# MegaAMP_Mk1.net
KiCad netlist of a schematic drawn in EAGLE
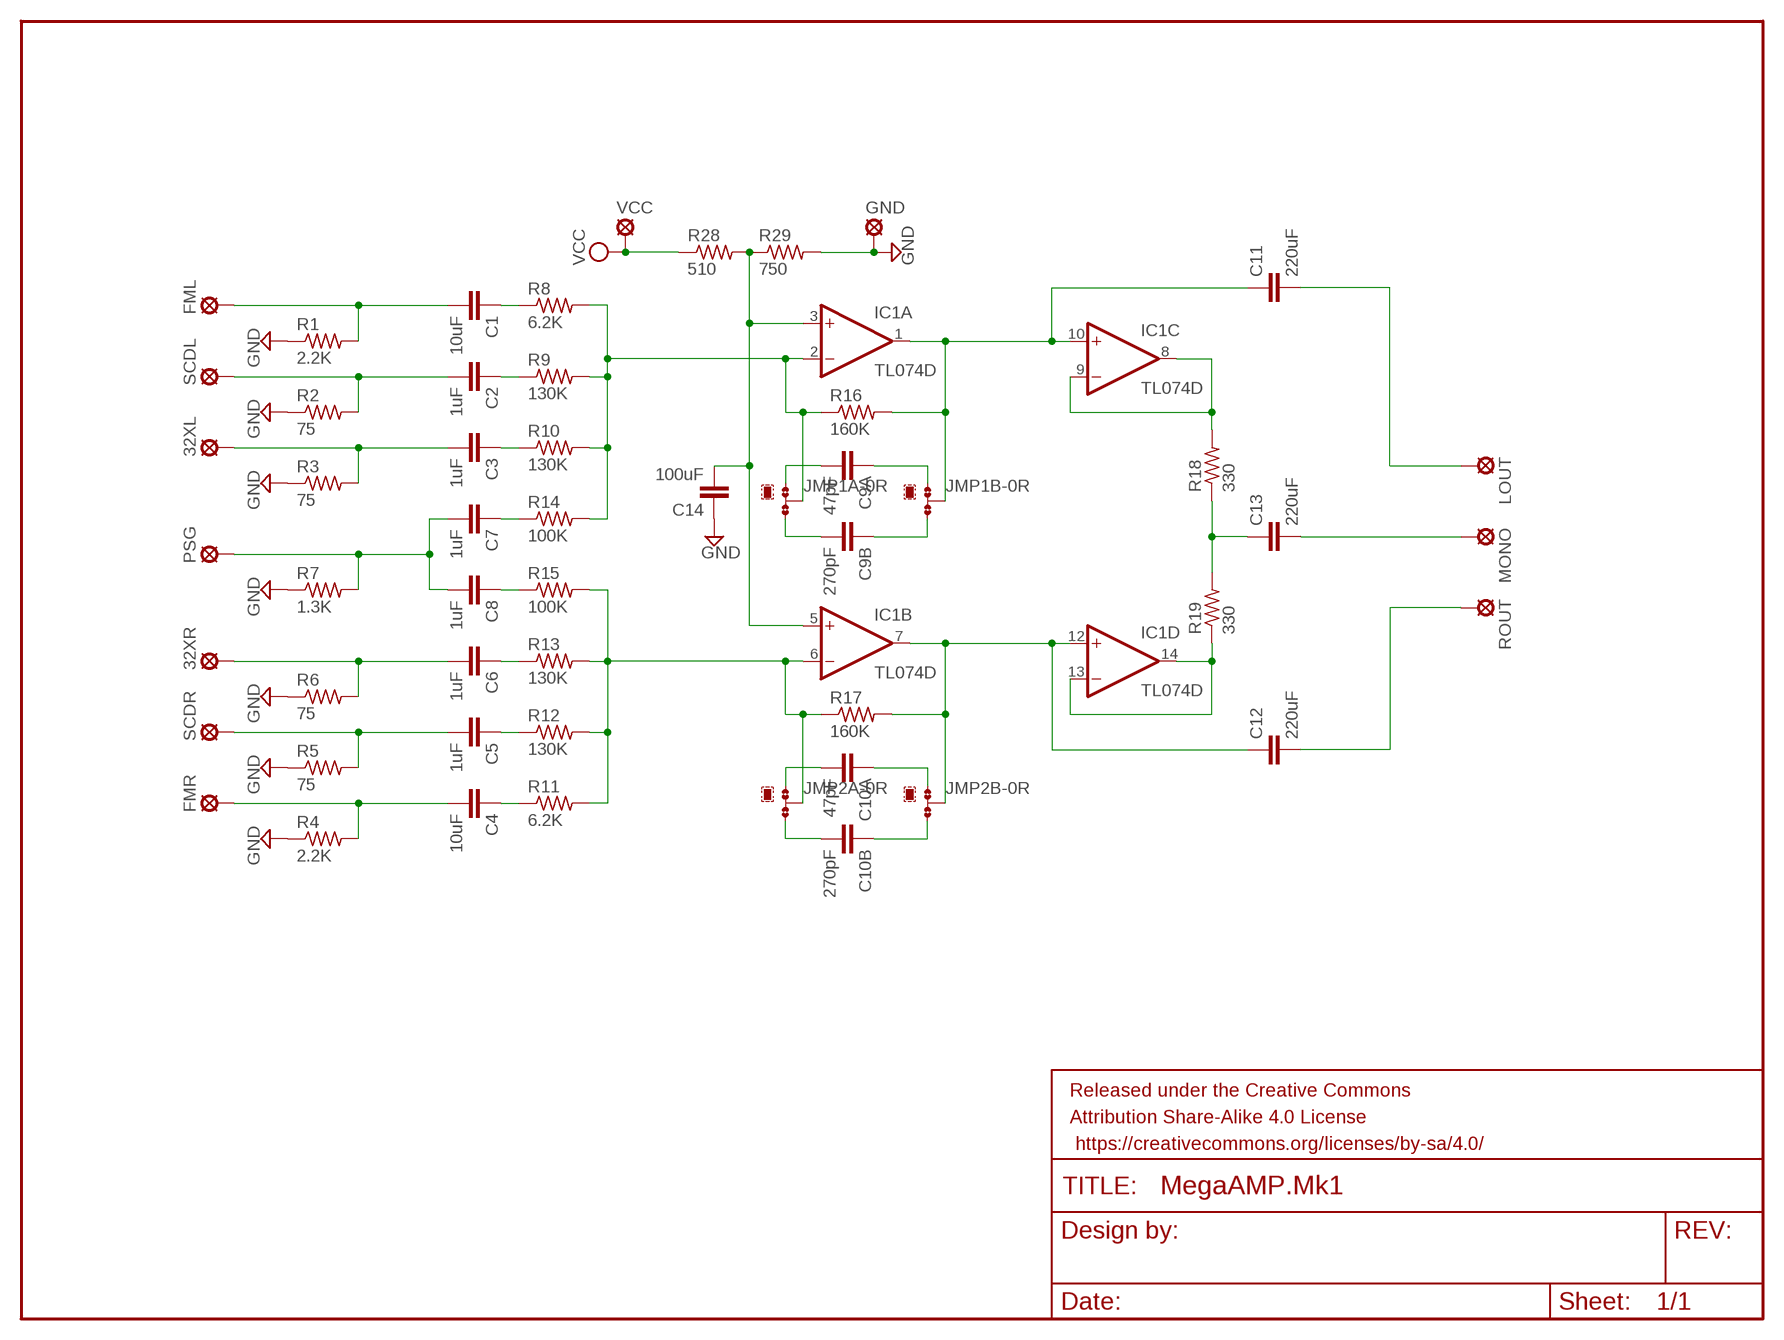
[diagram p0: schematic, sheet 1]

(export (version "E")
  (design (tool "Eeschema 10.0.6"))
  (components
    (comp (ref "32XL")
      (value "LSP13")
      (footprint "eagle-import:LSP13")
      (libsource (lib "eagle-import") (part "LSP13"))
    )
    (comp (ref "32XR")
      (value "LSP13")
      (footprint "eagle-import:LSP13")
      (libsource (lib "eagle-import") (part "LSP13"))
    )
    (comp (ref "C1")
      (value "10uF")
      (footprint "eagle-import:C0805")
      (libsource (lib "eagle-import") (part "C-EUC0805"))
    )
    (comp (ref "C2")
      (value "1uF")
      (footprint "eagle-import:C0805")
      (libsource (lib "eagle-import") (part "C-EUC0805"))
    )
    (comp (ref "C3")
      (value "1uF")
      (footprint "eagle-import:C0805")
      (libsource (lib "eagle-import") (part "C-EUC0805"))
    )
    (comp (ref "C4")
      (value "10uF")
      (footprint "eagle-import:C0805")
      (libsource (lib "eagle-import") (part "C-EUC0805"))
    )
    (comp (ref "C5")
      (value "1uF")
      (footprint "eagle-import:C0805")
      (libsource (lib "eagle-import") (part "C-EUC0805"))
    )
    (comp (ref "C6")
      (value "1uF")
      (footprint "eagle-import:C0805")
      (libsource (lib "eagle-import") (part "C-EUC0805"))
    )
    (comp (ref "C7")
      (value "1uF")
      (footprint "eagle-import:C0805")
      (libsource (lib "eagle-import") (part "C-EUC0805"))
    )
    (comp (ref "C8")
      (value "1uF")
      (footprint "eagle-import:C0805")
      (libsource (lib "eagle-import") (part "C-EUC0805"))
    )
    (comp (ref "C9A")
      (value "47pF")
      (footprint "eagle-import:C0805")
      (libsource (lib "eagle-import") (part "C-EUC0805"))
    )
    (comp (ref "C9B")
      (value "270pF")
      (footprint "eagle-import:C0805")
      (libsource (lib "eagle-import") (part "C-EUC0805"))
    )
    (comp (ref "C10A")
      (value "47pF")
      (footprint "eagle-import:C0805")
      (libsource (lib "eagle-import") (part "C-EUC0805"))
    )
    (comp (ref "C10B")
      (value "270pF")
      (footprint "eagle-import:C0805")
      (libsource (lib "eagle-import") (part "C-EUC0805"))
    )
    (comp (ref "C11")
      (value "220uF")
      (footprint "eagle-import:C1210")
      (libsource (lib "eagle-import") (part "resistor_C-EUC1210"))
    )
    (comp (ref "C12")
      (value "220uF")
      (footprint "eagle-import:C1210")
      (libsource (lib "eagle-import") (part "resistor_C-EUC1210"))
    )
    (comp (ref "C13")
      (value "220uF")
      (footprint "eagle-import:C1210")
      (libsource (lib "eagle-import") (part "resistor_C-EUC1210"))
    )
    (comp (ref "C14")
      (value "100uF")
      (footprint "eagle-import:C1206")
      (libsource (lib "eagle-import") (part "resistor_C-EUC1206"))
    )
    (comp (ref "FML")
      (value "LSP13")
      (footprint "eagle-import:LSP13")
      (libsource (lib "eagle-import") (part "LSP13"))
    )
    (comp (ref "FMR")
      (value "LSP13")
      (footprint "eagle-import:LSP13")
      (libsource (lib "eagle-import") (part "LSP13"))
    )
    (comp (ref "FRAME1")
      (value "FRAME-LETTER")
      (footprint "eagle-import:CREATIVE_COMMONS")
      (libsource (lib "eagle-import") (part "FRAME-LETTER"))
    )
    (comp (ref "GND")
      (value "LSP13")
      (footprint "eagle-import:LSP13")
      (libsource (lib "eagle-import") (part "LSP13"))
    )
    (comp (ref "IC1")
      (value "TL074D")
      (footprint "eagle-import:SO14")
      (libsource (lib "eagle-import") (part "TL074D"))
    )
    (comp (ref "JMP1A")
      (value "0R-JUMPA")
      (footprint "eagle-import:A0R-JMP")
      (libsource (lib "eagle-import") (part "0R-JUMPA"))
    )
    (comp (ref "JMP1B")
      (value "0R-JUMPA")
      (footprint "eagle-import:A0R-JMP")
      (libsource (lib "eagle-import") (part "0R-JUMPA"))
    )
    (comp (ref "JMP2A")
      (value "0R-JUMPA")
      (footprint "eagle-import:A0R-JMP")
      (libsource (lib "eagle-import") (part "0R-JUMPA"))
    )
    (comp (ref "JMP2B")
      (value "0R-JUMPA")
      (footprint "eagle-import:A0R-JMP")
      (libsource (lib "eagle-import") (part "0R-JUMPA"))
    )
    (comp (ref "LOUT")
      (value "LSP13")
      (footprint "eagle-import:LSP13")
      (libsource (lib "eagle-import") (part "LSP13"))
    )
    (comp (ref "MONO")
      (value "LSP13")
      (footprint "eagle-import:LSP13")
      (libsource (lib "eagle-import") (part "LSP13"))
    )
    (comp (ref "PSG")
      (value "LSP13")
      (footprint "eagle-import:LSP13")
      (libsource (lib "eagle-import") (part "LSP13"))
    )
    (comp (ref "R1")
      (value "2.2K")
      (footprint "eagle-import:R0805")
      (libsource (lib "eagle-import") (part "R-US_R0805"))
    )
    (comp (ref "R2")
      (value "75")
      (footprint "eagle-import:R0805")
      (libsource (lib "eagle-import") (part "R-US_R0805"))
    )
    (comp (ref "R3")
      (value "75")
      (footprint "eagle-import:R0805")
      (libsource (lib "eagle-import") (part "R-US_R0805"))
    )
    (comp (ref "R4")
      (value "2.2K")
      (footprint "eagle-import:R0805")
      (libsource (lib "eagle-import") (part "R-US_R0805"))
    )
    (comp (ref "R5")
      (value "75")
      (footprint "eagle-import:R0805")
      (libsource (lib "eagle-import") (part "R-US_R0805"))
    )
    (comp (ref "R6")
      (value "75")
      (footprint "eagle-import:R0805")
      (libsource (lib "eagle-import") (part "R-US_R0805"))
    )
    (comp (ref "R7")
      (value "1.3K")
      (footprint "eagle-import:R0805")
      (libsource (lib "eagle-import") (part "R-US_R0805"))
    )
    (comp (ref "R8")
      (value "6.2K")
      (footprint "eagle-import:R0805")
      (libsource (lib "eagle-import") (part "R-US_R0805"))
    )
    (comp (ref "R9")
      (value "130K")
      (footprint "eagle-import:R0805")
      (libsource (lib "eagle-import") (part "R-US_R0805"))
    )
    (comp (ref "R10")
      (value "130K")
      (footprint "eagle-import:R0805")
      (libsource (lib "eagle-import") (part "R-US_R0805"))
    )
    (comp (ref "R11")
      (value "6.2K")
      (footprint "eagle-import:R0805")
      (libsource (lib "eagle-import") (part "R-US_R0805"))
    )
    (comp (ref "R12")
      (value "130K")
      (footprint "eagle-import:R0805")
      (libsource (lib "eagle-import") (part "R-US_R0805"))
    )
    (comp (ref "R13")
      (value "130K")
      (footprint "eagle-import:R0805")
      (libsource (lib "eagle-import") (part "R-US_R0805"))
    )
    (comp (ref "R14")
      (value "100K")
      (footprint "eagle-import:R0805")
      (libsource (lib "eagle-import") (part "R-US_R0805"))
    )
    (comp (ref "R15")
      (value "100K")
      (footprint "eagle-import:R0805")
      (libsource (lib "eagle-import") (part "R-US_R0805"))
    )
    (comp (ref "R16")
      (value "160K")
      (footprint "eagle-import:R0805")
      (libsource (lib "eagle-import") (part "R-US_R0805"))
    )
    (comp (ref "R17")
      (value "160K")
      (footprint "eagle-import:R0805")
      (libsource (lib "eagle-import") (part "R-US_R0805"))
    )
    (comp (ref "R18")
      (value "330")
      (footprint "eagle-import:R0805")
      (libsource (lib "eagle-import") (part "R-US_R0805"))
    )
    (comp (ref "R19")
      (value "330")
      (footprint "eagle-import:R0805")
      (libsource (lib "eagle-import") (part "R-US_R0805"))
    )
    (comp (ref "R28")
      (value "510")
      (footprint "eagle-import:R0805")
      (libsource (lib "eagle-import") (part "R-US_R0805"))
    )
    (comp (ref "R29")
      (value "750")
      (footprint "eagle-import:R0805")
      (libsource (lib "eagle-import") (part "R-US_R0805"))
    )
    (comp (ref "ROUT")
      (value "LSP13")
      (footprint "eagle-import:LSP13")
      (libsource (lib "eagle-import") (part "LSP13"))
    )
    (comp (ref "SCDL")
      (value "LSP13")
      (footprint "eagle-import:LSP13")
      (libsource (lib "eagle-import") (part "LSP13"))
    )
    (comp (ref "SCDR")
      (value "LSP13")
      (footprint "eagle-import:LSP13")
      (libsource (lib "eagle-import") (part "LSP13"))
    )
    (comp (ref "VCC")
      (value "LSP13")
      (footprint "eagle-import:LSP13")
      (libsource (lib "eagle-import") (part "LSP13"))
    )
  )
  (nets
    (net (code "1") (name "GND") (class "Default")
      (node (ref "C14") (pin "1") (pinfunction "1_1") (pintype "passive"))
      (node (ref "GND") (pin "MP") (pinfunction "MP_MP") (pintype "passive"))
      (node (ref "R1") (pin "1") (pinfunction "1_1") (pintype "passive"))
      (node (ref "R2") (pin "1") (pinfunction "1_1") (pintype "passive"))
      (node (ref "R29") (pin "2") (pinfunction "2_2") (pintype "passive"))
      (node (ref "R3") (pin "1") (pinfunction "1_1") (pintype "passive"))
      (node (ref "R4") (pin "1") (pinfunction "1_1") (pintype "passive"))
      (node (ref "R5") (pin "1") (pinfunction "1_1") (pintype "passive"))
      (node (ref "R6") (pin "1") (pinfunction "1_1") (pintype "passive"))
      (node (ref "R7") (pin "1") (pinfunction "1_1") (pintype "passive"))
    )
    (net (code "2") (name "Net-(32XL-PadMP)") (class "Default")
      (node (ref "32XL") (pin "MP") (pinfunction "MP_MP") (pintype "passive"))
      (node (ref "C3") (pin "2") (pinfunction "2_2") (pintype "passive"))
      (node (ref "R3") (pin "2") (pinfunction "2_2") (pintype "passive"))
    )
    (net (code "3") (name "Net-(32XR-PadMP)") (class "Default")
      (node (ref "32XR") (pin "MP") (pinfunction "MP_MP") (pintype "passive"))
      (node (ref "C6") (pin "2") (pinfunction "2_2") (pintype "passive"))
      (node (ref "R6") (pin "2") (pinfunction "2_2") (pintype "passive"))
    )
    (net (code "4") (name "Net-(C1-Pad1)") (class "Default")
      (node (ref "C1") (pin "1") (pinfunction "1_1") (pintype "passive"))
      (node (ref "R8") (pin "1") (pinfunction "1_1") (pintype "passive"))
    )
    (net (code "5") (name "Net-(C1-Pad2)") (class "Default")
      (node (ref "C1") (pin "2") (pinfunction "2_2") (pintype "passive"))
      (node (ref "FML") (pin "MP") (pinfunction "MP_MP") (pintype "passive"))
      (node (ref "R1") (pin "2") (pinfunction "2_2") (pintype "passive"))
    )
    (net (code "6") (name "Net-(C2-Pad1)") (class "Default")
      (node (ref "C2") (pin "1") (pinfunction "1_1") (pintype "passive"))
      (node (ref "R9") (pin "1") (pinfunction "1_1") (pintype "passive"))
    )
    (net (code "7") (name "Net-(C2-Pad2)") (class "Default")
      (node (ref "C2") (pin "2") (pinfunction "2_2") (pintype "passive"))
      (node (ref "R2") (pin "2") (pinfunction "2_2") (pintype "passive"))
      (node (ref "SCDL") (pin "MP") (pinfunction "MP_MP") (pintype "passive"))
    )
    (net (code "8") (name "Net-(C3-Pad1)") (class "Default")
      (node (ref "C3") (pin "1") (pinfunction "1_1") (pintype "passive"))
      (node (ref "R10") (pin "1") (pinfunction "1_1") (pintype "passive"))
    )
    (net (code "9") (name "Net-(C4-Pad1)") (class "Default")
      (node (ref "C4") (pin "1") (pinfunction "1_1") (pintype "passive"))
      (node (ref "R11") (pin "1") (pinfunction "1_1") (pintype "passive"))
    )
    (net (code "10") (name "Net-(C4-Pad2)") (class "Default")
      (node (ref "C4") (pin "2") (pinfunction "2_2") (pintype "passive"))
      (node (ref "FMR") (pin "MP") (pinfunction "MP_MP") (pintype "passive"))
      (node (ref "R4") (pin "2") (pinfunction "2_2") (pintype "passive"))
    )
    (net (code "11") (name "Net-(C5-Pad1)") (class "Default")
      (node (ref "C5") (pin "1") (pinfunction "1_1") (pintype "passive"))
      (node (ref "R12") (pin "1") (pinfunction "1_1") (pintype "passive"))
    )
    (net (code "12") (name "Net-(C5-Pad2)") (class "Default")
      (node (ref "C5") (pin "2") (pinfunction "2_2") (pintype "passive"))
      (node (ref "R5") (pin "2") (pinfunction "2_2") (pintype "passive"))
      (node (ref "SCDR") (pin "MP") (pinfunction "MP_MP") (pintype "passive"))
    )
    (net (code "13") (name "Net-(C6-Pad1)") (class "Default")
      (node (ref "C6") (pin "1") (pinfunction "1_1") (pintype "passive"))
      (node (ref "R13") (pin "1") (pinfunction "1_1") (pintype "passive"))
    )
    (net (code "14") (name "Net-(C7-Pad1)") (class "Default")
      (node (ref "C7") (pin "1") (pinfunction "1_1") (pintype "passive"))
      (node (ref "R14") (pin "1") (pinfunction "1_1") (pintype "passive"))
    )
    (net (code "15") (name "Net-(C7-Pad2)") (class "Default")
      (node (ref "C7") (pin "2") (pinfunction "2_2") (pintype "passive"))
      (node (ref "C8") (pin "2") (pinfunction "2_2") (pintype "passive"))
      (node (ref "PSG") (pin "MP") (pinfunction "MP_MP") (pintype "passive"))
      (node (ref "R7") (pin "2") (pinfunction "2_2") (pintype "passive"))
    )
    (net (code "16") (name "Net-(C8-Pad1)") (class "Default")
      (node (ref "C8") (pin "1") (pinfunction "1_1") (pintype "passive"))
      (node (ref "R15") (pin "1") (pinfunction "1_1") (pintype "passive"))
    )
    (net (code "17") (name "Net-(C9A-Pad1)") (class "Default")
      (node (ref "C9A") (pin "1") (pinfunction "1_1") (pintype "passive"))
      (node (ref "JMP1B") (pin "1") (pinfunction "1_1") (pintype "passive"))
    )
    (net (code "18") (name "Net-(C9A-Pad2)") (class "Default")
      (node (ref "C9A") (pin "2") (pinfunction "2_2") (pintype "passive"))
      (node (ref "JMP1A") (pin "1") (pinfunction "1_1") (pintype "passive"))
    )
    (net (code "19") (name "Net-(C9B-Pad1)") (class "Default")
      (node (ref "C9B") (pin "1") (pinfunction "1_1") (pintype "passive"))
      (node (ref "JMP1B") (pin "3") (pinfunction "3_3") (pintype "passive"))
    )
    (net (code "20") (name "Net-(C9B-Pad2)") (class "Default")
      (node (ref "C9B") (pin "2") (pinfunction "2_2") (pintype "passive"))
      (node (ref "JMP1A") (pin "3") (pinfunction "3_3") (pintype "passive"))
    )
    (net (code "21") (name "Net-(C10A-Pad1)") (class "Default")
      (node (ref "C10A") (pin "1") (pinfunction "1_1") (pintype "passive"))
      (node (ref "JMP2B") (pin "1") (pinfunction "1_1") (pintype "passive"))
    )
    (net (code "22") (name "Net-(C10A-Pad2)") (class "Default")
      (node (ref "C10A") (pin "2") (pinfunction "2_2") (pintype "passive"))
      (node (ref "JMP2A") (pin "1") (pinfunction "1_1") (pintype "passive"))
    )
    (net (code "23") (name "Net-(C10B-Pad1)") (class "Default")
      (node (ref "C10B") (pin "1") (pinfunction "1_1") (pintype "passive"))
      (node (ref "JMP2B") (pin "3") (pinfunction "3_3") (pintype "passive"))
    )
    (net (code "24") (name "Net-(C10B-Pad2)") (class "Default")
      (node (ref "C10B") (pin "2") (pinfunction "2_2") (pintype "passive"))
      (node (ref "JMP2A") (pin "3") (pinfunction "3_3") (pintype "passive"))
    )
    (net (code "25") (name "Net-(C11-Pad2)") (class "Default")
      (node (ref "C11") (pin "2") (pinfunction "2_2") (pintype "passive"))
      (node (ref "LOUT") (pin "MP") (pinfunction "MP_MP") (pintype "passive"))
    )
    (net (code "26") (name "Net-(C12-Pad2)") (class "Default")
      (node (ref "C12") (pin "2") (pinfunction "2_2") (pintype "passive"))
      (node (ref "ROUT") (pin "MP") (pinfunction "MP_MP") (pintype "passive"))
    )
    (net (code "27") (name "Net-(C13-Pad1)") (class "Default")
      (node (ref "C13") (pin "1") (pinfunction "1_1") (pintype "passive"))
      (node (ref "R18") (pin "1") (pinfunction "1_1") (pintype "passive"))
      (node (ref "R19") (pin "2") (pinfunction "2_2") (pintype "passive"))
    )
    (net (code "28") (name "Net-(C13-Pad2)") (class "Default")
      (node (ref "C13") (pin "2") (pinfunction "2_2") (pintype "passive"))
      (node (ref "MONO") (pin "MP") (pinfunction "MP_MP") (pintype "passive"))
    )
    (net (code "29") (name "Net-(IC1A-+IN)") (class "Default")
      (node (ref "C14") (pin "2") (pinfunction "2_2") (pintype "passive"))
      (node (ref "IC1") (pin "3") (pinfunction "+IN_3") (pintype "input"))
      (node (ref "IC1") (pin "5") (pinfunction "+IN_5") (pintype "input"))
      (node (ref "R28") (pin "2") (pinfunction "2_2") (pintype "passive"))
      (node (ref "R29") (pin "1") (pinfunction "1_1") (pintype "passive"))
    )
    (net (code "30") (name "Net-(IC1A--IN)") (class "Default")
      (node (ref "IC1") (pin "2") (pinfunction "-IN_2") (pintype "input"))
      (node (ref "JMP1A") (pin "2") (pinfunction "2_2") (pintype "passive"))
      (node (ref "R10") (pin "2") (pinfunction "2_2") (pintype "passive"))
      (node (ref "R14") (pin "2") (pinfunction "2_2") (pintype "passive"))
      (node (ref "R16") (pin "1") (pinfunction "1_1") (pintype "passive"))
      (node (ref "R8") (pin "2") (pinfunction "2_2") (pintype "passive"))
      (node (ref "R9") (pin "2") (pinfunction "2_2") (pintype "passive"))
    )
    (net (code "31") (name "Net-(IC1A-OUT)") (class "Default")
      (node (ref "C11") (pin "1") (pinfunction "1_1") (pintype "passive"))
      (node (ref "IC1") (pin "1") (pinfunction "OUT_1") (pintype "output"))
      (node (ref "IC1") (pin "10") (pinfunction "+IN_10") (pintype "input"))
      (node (ref "JMP1B") (pin "2") (pinfunction "2_2") (pintype "passive"))
      (node (ref "R16") (pin "2") (pinfunction "2_2") (pintype "passive"))
    )
    (net (code "32") (name "Net-(IC1B--IN)") (class "Default")
      (node (ref "IC1") (pin "6") (pinfunction "-IN_6") (pintype "input"))
      (node (ref "JMP2A") (pin "2") (pinfunction "2_2") (pintype "passive"))
      (node (ref "R11") (pin "2") (pinfunction "2_2") (pintype "passive"))
      (node (ref "R12") (pin "2") (pinfunction "2_2") (pintype "passive"))
      (node (ref "R13") (pin "2") (pinfunction "2_2") (pintype "passive"))
      (node (ref "R15") (pin "2") (pinfunction "2_2") (pintype "passive"))
      (node (ref "R17") (pin "1") (pinfunction "1_1") (pintype "passive"))
    )
    (net (code "33") (name "Net-(IC1B-OUT)") (class "Default")
      (node (ref "C12") (pin "1") (pinfunction "1_1") (pintype "passive"))
      (node (ref "IC1") (pin "12") (pinfunction "+IN_12") (pintype "input"))
      (node (ref "IC1") (pin "7") (pinfunction "OUT_7") (pintype "output"))
      (node (ref "JMP2B") (pin "2") (pinfunction "2_2") (pintype "passive"))
      (node (ref "R17") (pin "2") (pinfunction "2_2") (pintype "passive"))
    )
    (net (code "34") (name "Net-(IC1C--IN)") (class "Default")
      (node (ref "IC1") (pin "8") (pinfunction "OUT_8") (pintype "output"))
      (node (ref "IC1") (pin "9") (pinfunction "-IN_9") (pintype "input"))
      (node (ref "R18") (pin "2") (pinfunction "2_2") (pintype "passive"))
    )
    (net (code "35") (name "Net-(IC1D--IN)") (class "Default")
      (node (ref "IC1") (pin "13") (pinfunction "-IN_13") (pintype "input"))
      (node (ref "IC1") (pin "14") (pinfunction "OUT_14") (pintype "output"))
      (node (ref "R19") (pin "1") (pinfunction "1_1") (pintype "passive"))
    )
    (net (code "36") (name "VCC") (class "Default")
      (node (ref "R28") (pin "1") (pinfunction "1_1") (pintype "passive"))
      (node (ref "VCC") (pin "MP") (pinfunction "MP_MP") (pintype "passive"))
    )
  )
)
